# snowflake_r2.net
KiCad netlist of a schematic drawn in Altium Designer
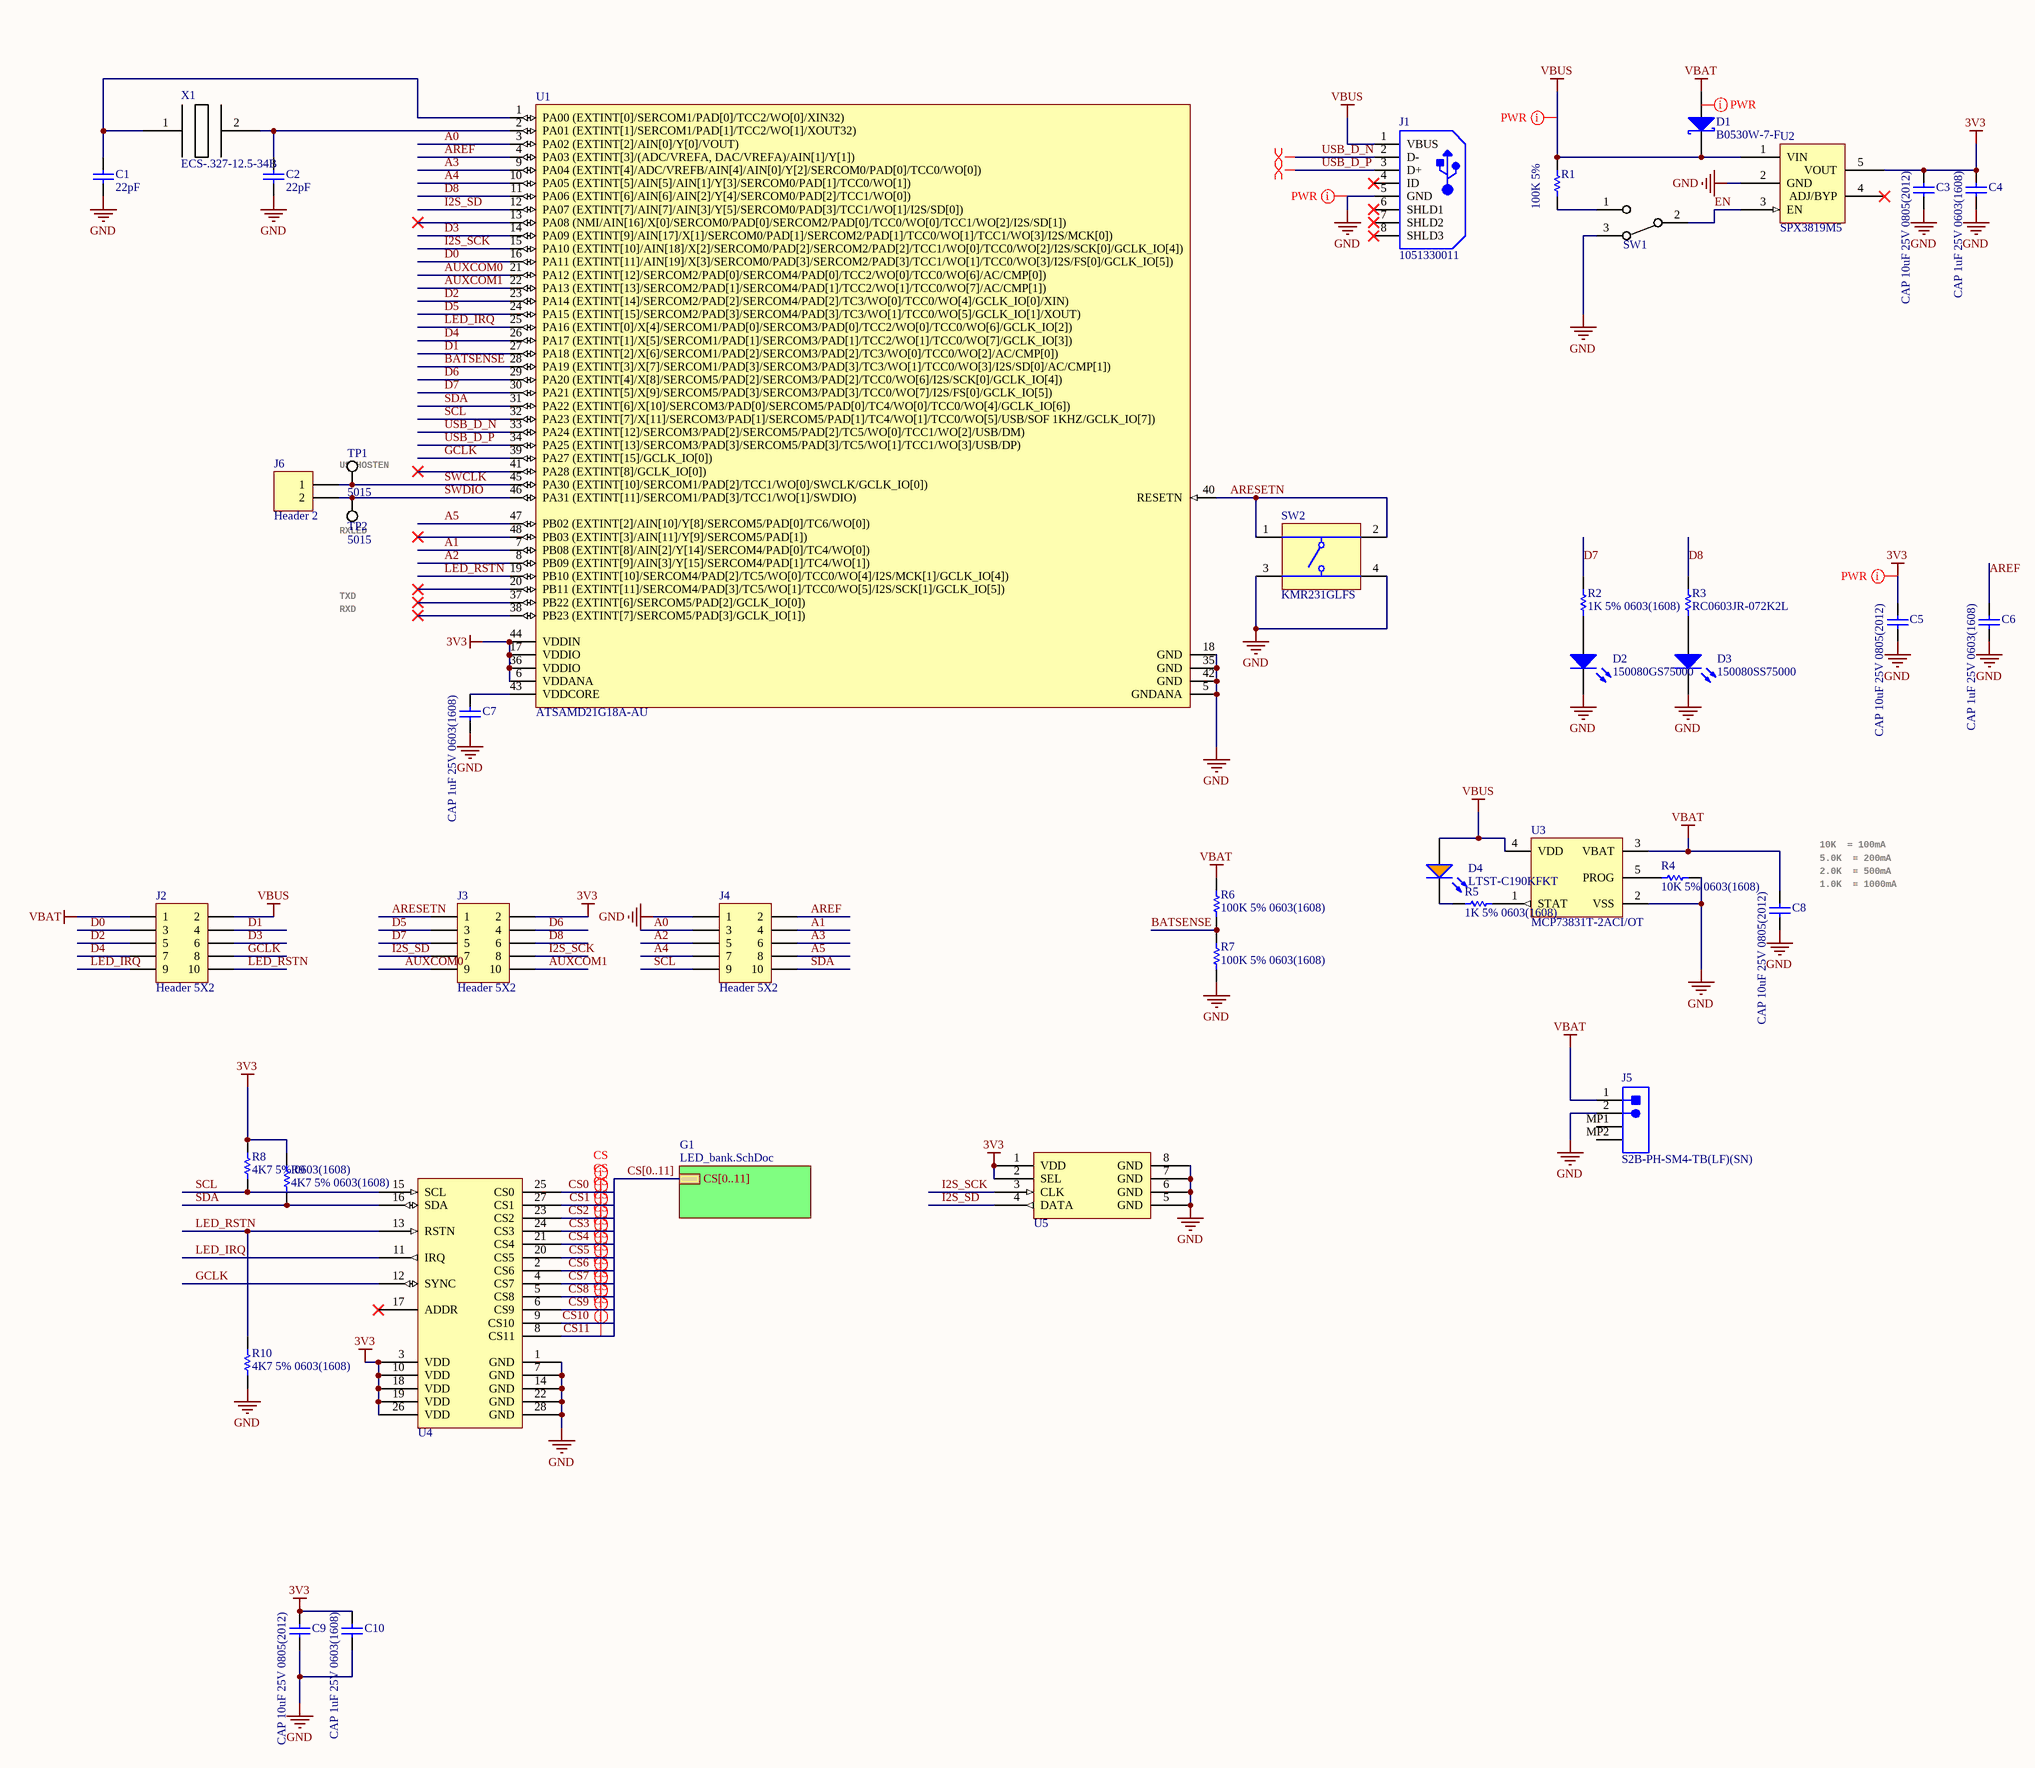
[diagram p0: snowflake_r2.SchDoc]

(export (version "E")
  (design (tool "Eeschema 10.0.6"))
  (components
    (comp (ref "C1")
      (value "22pF")
      (footprint "CAPC0603(1608)100_L")
      (description "0603 (1608 Metric) Chip Capacitor")
      (libsource (lib "Altium Content Vault") (part "CMP-1590-00005-1"))
    )
    (comp (ref "C2")
      (value "22pF")
      (footprint "CAPC0603(1608)100_L")
      (description "0603 (1608 Metric) Chip Capacitor")
      (libsource (lib "Altium Content Vault") (part "CAP_5"))
    )
    (comp (ref "C3")
      (value "CAP 10uF 25V 0805(2012)")
      (footprint "CAPC0805(2012)145_N")
      (description "CAP 10uF 25V ±10% 0805 (2012 Metric) Thickness 1.45mm SMD")
      (fields (field (name "TOLERANCE") "Â±10%"))
      (libsource (lib "Altium Content Vault") (part "CAP"))
    )
    (comp (ref "C4")
      (value "CAP 1uF 25V 0603(1608)")
      (footprint "CAPC0603(1608)100_M")
      (description "CAP 1uF 25V ±20% 0603 (1608 Metric) Thickness 1mm SMD")
      (fields (field (name "TOLERANCE") "Â±20%"))
      (libsource (lib "Altium Content Vault") (part "CAP"))
    )
    (comp (ref "C5")
      (value "CAP 10uF 25V 0805(2012)")
      (footprint "CAPC0805(2012)145_N")
      (description "CAP 10uF 25V ±10% 0805 (2012 Metric) Thickness 1.45mm SMD")
      (fields (field (name "TOLERANCE") "Â±10%"))
      (libsource (lib "Altium Content Vault") (part "CAP"))
    )
    (comp (ref "C6")
      (value "CAP 1uF 25V 0603(1608)")
      (footprint "CAPC0603(1608)100_M")
      (description "CAP 1uF 25V ±20% 0603 (1608 Metric) Thickness 1mm SMD")
      (fields (field (name "TOLERANCE") "Â±20%"))
      (libsource (lib "Altium Content Vault") (part "CAP"))
    )
    (comp (ref "C7")
      (value "CAP 1uF 25V 0603(1608)")
      (footprint "CAPC0603(1608)100_M")
      (description "CAP 1uF 25V ±20% 0603 (1608 Metric) Thickness 1mm SMD")
      (fields (field (name "TOLERANCE") "Â±20%"))
      (libsource (lib "Altium Content Vault") (part "CAP"))
    )
    (comp (ref "C8")
      (value "CAP 10uF 25V 0805(2012)")
      (footprint "CAPC0805(2012)145_N")
      (description "CAP 10uF 25V ±10% 0805 (2012 Metric) Thickness 1.45mm SMD")
      (fields (field (name "TOLERANCE") "Â±10%"))
      (libsource (lib "Altium Content Vault") (part "CAP"))
    )
    (comp (ref "C9")
      (value "CAP 10uF 25V 0805(2012)")
      (footprint "CAPC0805(2012)145_N")
      (description "CAP 10uF 25V ±10% 0805 (2012 Metric) Thickness 1.45mm SMD")
      (fields (field (name "TOLERANCE") "Â±10%"))
      (libsource (lib "Altium Content Vault") (part "CAP"))
    )
    (comp (ref "C10")
      (value "CAP 1uF 25V 0603(1608)")
      (footprint "CAPC0603(1608)100_M")
      (description "CAP 1uF 25V ±20% 0603 (1608 Metric) Thickness 1mm SMD")
      (fields (field (name "TOLERANCE") "Â±20%"))
      (libsource (lib "Altium Content Vault") (part "CAP"))
    )
    (comp (ref "D1")
      (value "B0530W-7-F")
      (footprint "DIOD-SOD-123-2-A_V")
      (description "Schottky Barrier Rectifier, 0.5 A, 30 V, -65 to 125 degC, 2-Pin SOD-123, RoHS, Tape and Reel")
      (fields (field (name "MANUFACTURER") "DiodesIncorporated"))
      (libsource (lib "Altium Content Vault") (part "DSKY-AK-2"))
    )
    (comp (ref "D2")
      (value "150080GS75000")
      (footprint "0805_A")
      (description "SMD mono-color Chip LED, WL-SMCW, Green")
      (fields (field (name "MANUFACTURER") "Wuerth Elektronik"))
      (libsource (lib "Altium Content Vault") (part "WE-LED_K1A2-2"))
    )
    (comp (ref "D3")
      (value "150080SS75000")
      (footprint "0805_A")
      (description "SMD mono-color Chip LED, WL-SMCW, Super Red")
      (fields (field (name "MANUFACTURER") "Wuerth Elektronik"))
      (libsource (lib "Altium Content Vault") (part "WE-LED_K1A2-2"))
    )
    (comp (ref "D4")
      (value "LTST-C190KFKT")
      (footprint "LTST-C190KFKT_V")
      (description "LED Uni-Color Orange, 75 mW, 30 mA, -35 to 85 degC, 2-Pin SMD, RoHS, Tape and Reel")
      (fields (field (name "TOLERANCE") "1%"))
      (libsource (lib "Altium Content Vault") (part "LED-ORANGE-AK-2"))
    )
    (comp (ref "J1")
      (value "1051330011")
      (footprint "MOLX-1051330011-5_V")
      (description "Micro-B USB Vertical Type, -30 to 85 degC, 5-Pin SMD, RoHS, Tape and Reel")
      (fields (field (name "MANUFACTURER") "Molex"))
      (libsource (lib "Altium Content Vault") (part "CMP-2000-05241-1"))
    )
    (comp (ref "J2")
      (value "Header 5X2")
      (footprint "HDR2X5")
      (description "Header, 5-Pin, Dual row")
      (fields (field (name "PUBLISHER") "Altium Limited"))
      (libsource (lib "Miscellaneous Connectors") (part "Header 5X2"))
    )
    (comp (ref "J3")
      (value "Header 5X2")
      (footprint "HDR2X5")
      (description "Header, 5-Pin, Dual row")
      (fields (field (name "PUBLISHER") "Altium Limited"))
      (libsource (lib "Miscellaneous Connectors") (part "Header 5X2"))
    )
    (comp (ref "J4")
      (value "Header 5X2")
      (footprint "HDR2X5")
      (description "Header, 5-Pin, Dual row")
      (fields (field (name "PUBLISHER") "Altium Limited"))
      (libsource (lib "Miscellaneous Connectors") (part "Header 5X2"))
    )
    (comp (ref "J5")
      (value "S2B-PH-SM4-TB(LF)(SN)")
      (footprint "JST- S2B-PH-SM4-TB(LF)(SN)-2_V")
      (description "Male Header, Pitch 2 mm, 1 x 2 Position, Height 5.5 mm, -25 to 85 degC, RoHS, Tape and Reel")
      (libsource (lib "Altium Content Vault") (part "CMP-1755-00001-1"))
    )
    (comp (ref "J6")
      (value "Header 2")
      (footprint "HDR1X2")
      (description "Header, 2-Pin")
      (fields (field (name "PUBLISHER") "Altium Limited"))
      (libsource (lib "Miscellaneous Connectors") (part "Header 2"))
    )
    (comp (ref "R1")
      (value "100K 5%")
      (footprint "RESC0603(1608)_N")
      (description "100K 0.1W 5% 0603 (1608 Metric)  SMD")
      (fields (field (name "TOLERANCE") "5 %") (field (name "POWER") "0.1 W"))
      (libsource (lib "Altium Content Vault") (part "RES"))
    )
    (comp (ref "R2")
      (value "1K 5% 0603(1608)")
      (footprint "RESC0603(1608)_L")
      (description "1K 0.1W 5% 0603 (1608 Metric)  SMD")
      (fields (field (name "TOLERANCE") "5 %") (field (name "POWER") "0.1 W"))
      (libsource (lib "Altium Content Vault") (part "RES"))
    )
    (comp (ref "R3")
      (value "RC0603JR-072K2L")
      (footprint "RESC1608X55X25LL10T15")
      (description "Chip Resistor, 2.2 KOhm, +/- 5%, 0.1 W, -55 to 155 degC, 0603 (1608 Metric), RoHS, Tape and Reel")
      (fields (field (name "MANUFACTURER") "Yageo") (field (name "TOLERANCE") "5%"))
      (libsource (lib "Altium Content Vault") (part "RES-2"))
    )
    (comp (ref "R4")
      (value "10K 5% 0603(1608)")
      (footprint "RESC0603(1608)_N")
      (description "10K 0.1W 5% 0603 (1608 Metric)  SMD")
      (fields (field (name "TOLERANCE") "5 %") (field (name "POWER") "0.1 W"))
      (libsource (lib "Altium Content Vault") (part "RES"))
    )
    (comp (ref "R5")
      (value "1K 5% 0603(1608)")
      (footprint "RESC0603(1608)_L")
      (description "1K 0.1W 5% 0603 (1608 Metric)  SMD")
      (fields (field (name "TOLERANCE") "5 %") (field (name "POWER") "0.1 W"))
      (libsource (lib "Altium Content Vault") (part "RES"))
    )
    (comp (ref "R6")
      (value "100K 5% 0603(1608)")
      (footprint "RESC0603(1608)_N")
      (description "100K 0.1W 5% 0603 (1608 Metric)  SMD")
      (fields (field (name "TOLERANCE") "5 %") (field (name "POWER") "0.1 W"))
      (libsource (lib "Altium Content Vault") (part "RES"))
    )
    (comp (ref "R7")
      (value "100K 5% 0603(1608)")
      (footprint "RESC0603(1608)_N")
      (description "100K 0.1W 5% 0603 (1608 Metric)  SMD")
      (fields (field (name "TOLERANCE") "5 %") (field (name "POWER") "0.1 W"))
      (libsource (lib "Altium Content Vault") (part "RES"))
    )
    (comp (ref "R8")
      (value "4K7 5% 0603(1608)")
      (footprint "RESC0603(1608)_N")
      (description "4K7 0.1W 5% 0603 (1608 Metric)  SMD")
      (fields (field (name "TOLERANCE") "5 %") (field (name "POWER") "0.1 W"))
      (libsource (lib "Altium Content Vault") (part "RES"))
    )
    (comp (ref "R9")
      (value "4K7 5% 0603(1608)")
      (footprint "RESC0603(1608)_N")
      (description "4K7 0.1W 5% 0603 (1608 Metric)  SMD")
      (fields (field (name "TOLERANCE") "5 %") (field (name "POWER") "0.1 W"))
      (libsource (lib "Altium Content Vault") (part "RES"))
    )
    (comp (ref "R10")
      (value "4K7 5% 0603(1608)")
      (footprint "RESC0603(1608)_N")
      (description "4K7 0.1W 5% 0603 (1608 Metric)  SMD")
      (fields (field (name "TOLERANCE") "5 %") (field (name "POWER") "0.1 W"))
      (libsource (lib "Altium Content Vault") (part "RES"))
    )
    (comp (ref "SW1")
      (value "JS102011JCQN")
      (footprint "JS102011JCQN")
      (description "SWITCH SPDT PCB")
      (libsource (lib "snowflake") (part "SW-SPDT"))
    )
    (comp (ref "SW2")
      (value "KMR231GLFS")
      (footprint "CKCP-KMR231GLFS")
      (description "Switch Tactile, SPST, 50 mA, 32 V, -40 to 85 degC, 4-Pin SMD, RoHS, Tape and Reel")
      (fields (field (name "MANUFACTURER") "C&K Components"))
      (libsource (lib "Altium Content Vault") (part "SW-SPST-4_A"))
    )
    (comp (ref "TP1")
      (value "5015")
      (footprint "KSTN-5015_V")
      (description "Test Point, White, SMT")
      (fields (field (name "MANUFACTURER") "Keystone"))
      (libsource (lib "Altium Content Vault") (part "TESTPOINT_WHITE"))
    )
    (comp (ref "TP2")
      (value "5015")
      (footprint "KSTN-5015_V")
      (description "Test Point, White, SMT")
      (fields (field (name "MANUFACTURER") "Keystone"))
      (libsource (lib "Altium Content Vault") (part "TESTPOINT_WHITE"))
    )
    (comp (ref "U1")
      (value "ATSAMD21G18A-AU")
      (footprint "ATML-TQFP48_M")
      (fields (field (name "MANUFACTURER") "Atmel"))
      (libsource (lib "Altium Content Vault") (part "ATML-ATSAMD21G18_17_16_15A-TQFP48"))
    )
    (comp (ref "U2")
      (value "SPX3819M5")
      (footprint "SOT95P280X145-5N")
      (description "IC REG LINEAR 3.3V 500MA SOT23-5")
      (libsource (lib "snowflake") (part "SPX3819M5"))
    )
    (comp (ref "U3")
      (value "MCP73831T-2ACI/OT")
      (footprint "SOT-23-OT5_M")
      (libsource (lib "Altium Content Vault") (part "PM-BM-MCP73831-SOT5"))
    )
    (comp (ref "U4")
      (value "AS1130_BTST")
      (footprint "TSOP65P640X120-28N")
      (description "IC LED DRVR MATRIX 28TSSOP")
      (libsource (lib "snowflake") (part "AS1130_BTST"))
    )
    (comp (ref "U5")
      (value "SPK0415HM4H-B-7")
      (footprint "SPK0415HM4H-B-7")
      (description "MIC MEMS DIGITAL PDM OMNI -26DB")
      (libsource (lib "snowflake") (part "SPK0415HM4H-B-7"))
    )
    (comp (ref "X1")
      (value "ECS-.327-12.5-34B")
      (footprint "ECX-31B")
      (description "XTAL 32.768KHZ 12.5PF SMD")
      (libsource (lib "snowflake") (part "ECS-.327-12.5-34B"))
    )
  )
  (nets
    (net (code "1") (name "/A0") (class "Default")
      (node (ref "J4") (pin "3") (pinfunction "3_3") (pintype "passive"))
      (node (ref "U1") (pin "3") (pinfunction "PA02_(EXTINT[2]/AIN[0]/Y[0]/VOUT)_3") (pintype "bidirectional"))
    )
    (net (code "2") (name "/A1") (class "Default")
      (node (ref "J4") (pin "4") (pinfunction "4_4") (pintype "passive"))
      (node (ref "U1") (pin "7") (pinfunction "PB08_(EXTINT[8]/AIN[2]/Y[14]/SERCOM4/PAD[0]/TC4/WO[0])_7") (pintype "bidirectional"))
    )
    (net (code "3") (name "/A2") (class "Default")
      (node (ref "J4") (pin "5") (pinfunction "5_5") (pintype "passive"))
      (node (ref "U1") (pin "8") (pinfunction "PB09_(EXTINT[9]/AIN[3]/Y[15]/SERCOM4/PAD[1]/TC4/WO[1])_8") (pintype "bidirectional"))
    )
    (net (code "4") (name "/A3") (class "Default")
      (node (ref "J4") (pin "6") (pinfunction "6_6") (pintype "passive"))
      (node (ref "U1") (pin "9") (pinfunction "PA04_(EXTINT[4]/ADC/VREFB/AIN[4]/AIN[0]/Y[2]/SERCOM0/PAD[0]/TCC0/WO[0])_9") (pintype "bidirectional"))
    )
    (net (code "5") (name "/A4") (class "Default")
      (node (ref "J4") (pin "7") (pinfunction "7_7") (pintype "passive"))
      (node (ref "U1") (pin "10") (pinfunction "PA05_(EXTINT[5]/AIN[5]/AIN[1]/Y[3]/SERCOM0/PAD[1]/TCC0/WO[1])_10") (pintype "bidirectional"))
    )
    (net (code "6") (name "/A5") (class "Default")
      (node (ref "J4") (pin "8") (pinfunction "8_8") (pintype "passive"))
      (node (ref "U1") (pin "47") (pinfunction "PB02_(EXTINT[2]/AIN[10]/Y[8]/SERCOM5/PAD[0]/TC6/WO[0])_47") (pintype "bidirectional"))
    )
    (net (code "7") (name "/AREF") (class "Default")
      (node (ref "C6") (pin "2") (pinfunction "2_2") (pintype "passive"))
      (node (ref "J4") (pin "2") (pinfunction "2_2") (pintype "passive"))
      (node (ref "U1") (pin "4") (pinfunction "PA03_(EXTINT[3]/(ADC/VREFA,_DAC/VREFA)/AIN[1]/Y[1])_4") (pintype "bidirectional"))
    )
    (net (code "8") (name "/ARESETN") (class "Default")
      (node (ref "J3") (pin "1") (pinfunction "1_1") (pintype "passive"))
      (node (ref "SW2") (pin "1") (pinfunction "1_1") (pintype "passive"))
      (node (ref "SW2") (pin "2") (pinfunction "2_2") (pintype "passive"))
      (node (ref "U1") (pin "40") (pinfunction "RESETN_40") (pintype "input"))
    )
    (net (code "9") (name "/AUXCOM0") (class "Default")
      (node (ref "J3") (pin "9") (pinfunction "9_9") (pintype "passive"))
      (node (ref "U1") (pin "21") (pinfunction "PA12_(EXTINT[12]/SERCOM2/PAD[0]/SERCOM4/PAD[0]/TCC2/WO[0]/TCC0/WO[6]/AC/CMP[0])_21") (pintype "bidirectional"))
    )
    (net (code "10") (name "/AUXCOM1") (class "Default")
      (node (ref "J3") (pin "10") (pinfunction "10_10") (pintype "passive"))
      (node (ref "U1") (pin "22") (pinfunction "PA13_(EXTINT[13]/SERCOM2/PAD[1]/SERCOM4/PAD[1]/TCC2/WO[1]/TCC0/WO[7]/AC/CMP[1])_22") (pintype "bidirectional"))
    )
    (net (code "11") (name "/BATSENSE") (class "Default")
      (node (ref "R6") (pin "1") (pinfunction "1_1") (pintype "passive"))
      (node (ref "R7") (pin "2") (pinfunction "2_2") (pintype "passive"))
      (node (ref "U1") (pin "28") (pinfunction "PA19_(EXTINT[3]/X[7]/SERCOM1/PAD[3]/SERCOM3/PAD[3]/TC3/WO[1]/TCC0/WO[3]/I2S/SD[0]/AC/CMP[1])_28") (pintype "bidirectional"))
    )
    (net (code "12") (name "/CS0") (class "Default")
      (node (ref "U4") (pin "25") (pinfunction "CS0_25") (pintype "passive"))
    )
    (net (code "13") (name "/CS1") (class "Default")
      (node (ref "U4") (pin "27") (pinfunction "CS1_27") (pintype "passive"))
    )
    (net (code "14") (name "/CS2") (class "Default")
      (node (ref "U4") (pin "23") (pinfunction "CS2_23") (pintype "passive"))
    )
    (net (code "15") (name "/CS3") (class "Default")
      (node (ref "U4") (pin "24") (pinfunction "CS3_24") (pintype "passive"))
    )
    (net (code "16") (name "/CS4") (class "Default")
      (node (ref "U4") (pin "21") (pinfunction "CS4_21") (pintype "passive"))
    )
    (net (code "17") (name "/CS5") (class "Default")
      (node (ref "U4") (pin "20") (pinfunction "CS5_20") (pintype "passive"))
    )
    (net (code "18") (name "/CS6") (class "Default")
      (node (ref "U4") (pin "2") (pinfunction "CS6_2") (pintype "passive"))
    )
    (net (code "19") (name "/CS7") (class "Default")
      (node (ref "U4") (pin "4") (pinfunction "CS7_4") (pintype "passive"))
    )
    (net (code "20") (name "/CS8") (class "Default")
      (node (ref "U4") (pin "5") (pinfunction "CS8_5") (pintype "passive"))
    )
    (net (code "21") (name "/CS9") (class "Default")
      (node (ref "U4") (pin "6") (pinfunction "CS9_6") (pintype "passive"))
    )
    (net (code "22") (name "/CS10") (class "Default")
      (node (ref "U4") (pin "9") (pinfunction "CS10_9") (pintype "passive"))
    )
    (net (code "23") (name "/CS11") (class "Default")
      (node (ref "U4") (pin "8") (pinfunction "CS11_8") (pintype "passive"))
    )
    (net (code "25") (name "/D0") (class "Default")
      (node (ref "J2") (pin "3") (pinfunction "3_3") (pintype "passive"))
      (node (ref "U1") (pin "16") (pinfunction "PA11_(EXTINT[11]/AIN[19]/X[3]/SERCOM0/PAD[3]/SERCOM2/PAD[3]/TCC1/WO[1]/TCC0/WO[3]/I2S/FS[0]/GCLK_IO[5])_16") (pintype "bidirectional"))
    )
    (net (code "26") (name "/D1") (class "Default")
      (node (ref "J2") (pin "4") (pinfunction "4_4") (pintype "passive"))
      (node (ref "U1") (pin "27") (pinfunction "PA18_(EXTINT[2]/X[6]/SERCOM1/PAD[2]/SERCOM3/PAD[2]/TC3/WO[0]/TCC0/WO[2]/AC/CMP[0])_27") (pintype "bidirectional"))
    )
    (net (code "27") (name "/D2") (class "Default")
      (node (ref "J2") (pin "5") (pinfunction "5_5") (pintype "passive"))
      (node (ref "U1") (pin "23") (pinfunction "PA14_(EXTINT[14]/SERCOM2/PAD[2]/SERCOM4/PAD[2]/TC3/WO[0]/TCC0/WO[4]/GCLK_IO[0]/XIN)_23") (pintype "bidirectional"))
    )
    (net (code "28") (name "/D3") (class "Default")
      (node (ref "J2") (pin "6") (pinfunction "6_6") (pintype "passive"))
      (node (ref "U1") (pin "14") (pinfunction "PA09_(EXTINT[9]/AIN[17]/X[1]/SERCOM0/PAD[1]/SERCOM2/PAD[1]/TCC0/WO[1]/TCC1/WO[3]/I2S/MCK[0])_14") (pintype "bidirectional"))
    )
    (net (code "29") (name "/D4") (class "Default")
      (node (ref "J2") (pin "7") (pinfunction "7_7") (pintype "passive"))
      (node (ref "U1") (pin "26") (pinfunction "PA17_(EXTINT[1]/X[5]/SERCOM1/PAD[1]/SERCOM3/PAD[1]/TCC2/WO[1]/TCC0/WO[7]/GCLK_IO[3])_26") (pintype "bidirectional"))
    )
    (net (code "30") (name "/D5") (class "Default")
      (node (ref "J3") (pin "3") (pinfunction "3_3") (pintype "passive"))
      (node (ref "U1") (pin "24") (pinfunction "PA15_(EXTINT[15]/SERCOM2/PAD[3]/SERCOM4/PAD[3]/TC3/WO[1]/TCC0/WO[5]/GCLK_IO[1]/XOUT)_24") (pintype "bidirectional"))
    )
    (net (code "31") (name "/D6") (class "Default")
      (node (ref "J3") (pin "4") (pinfunction "4_4") (pintype "passive"))
      (node (ref "U1") (pin "29") (pinfunction "PA20_(EXTINT[4]/X[8]/SERCOM5/PAD[2]/SERCOM3/PAD[2]/TCC0/WO[6]/I2S/SCK[0]/GCLK_IO[4])_29") (pintype "bidirectional"))
    )
    (net (code "32") (name "/D7") (class "Default")
      (node (ref "J3") (pin "5") (pinfunction "5_5") (pintype "passive"))
      (node (ref "R2") (pin "2") (pinfunction "2_2") (pintype "passive"))
      (node (ref "U1") (pin "30") (pinfunction "PA21_(EXTINT[5]/X[9]/SERCOM5/PAD[3]/SERCOM3/PAD[3]/TCC0/WO[7]/I2S/FS[0]/GCLK_IO[5])_30") (pintype "bidirectional"))
    )
    (net (code "33") (name "/D8") (class "Default")
      (node (ref "J3") (pin "6") (pinfunction "6_6") (pintype "passive"))
      (node (ref "R3") (pin "2") (pinfunction "2_2") (pintype "passive"))
      (node (ref "U1") (pin "11") (pinfunction "PA06_(EXTINT[6]/AIN[6]/AIN[2]/Y[4]/SERCOM0/PAD[2]/TCC1/WO[0])_11") (pintype "bidirectional"))
    )
    (net (code "34") (name "/EN") (class "Default")
      (node (ref "SW1") (pin "2") (pinfunction "2_2") (pintype "passive"))
      (node (ref "U2") (pin "3") (pinfunction "EN_3") (pintype "input"))
    )
    (net (code "35") (name "/GCLK") (class "Default")
      (node (ref "J2") (pin "8") (pinfunction "8_8") (pintype "passive"))
      (node (ref "U1") (pin "39") (pinfunction "PA27_(EXTINT[15]/GCLK_IO[0])_39") (pintype "bidirectional"))
      (node (ref "U4") (pin "12") (pinfunction "SYNC_12") (pintype "bidirectional"))
    )
    (net (code "36") (name "/I2S_SCK") (class "Default")
      (node (ref "J3") (pin "8") (pinfunction "8_8") (pintype "passive"))
      (node (ref "U1") (pin "15") (pinfunction "PA10_(EXTINT[10]/AIN[18]/X[2]/SERCOM0/PAD[2]/SERCOM2/PAD[2]/TCC1/WO[0]/TCC0/WO[2]/I2S/SCK[0]/GCLK_IO[4])_15") (pintype "bidirectional"))
      (node (ref "U5") (pin "3") (pinfunction "CLK_3") (pintype "input"))
    )
    (net (code "37") (name "/I2S_SD") (class "Default")
      (node (ref "J3") (pin "7") (pinfunction "7_7") (pintype "passive"))
      (node (ref "U1") (pin "12") (pinfunction "PA07_(EXTINT[7]/AIN[7]/AIN[3]/Y[5]/SERCOM0/PAD[3]/TCC1/WO[1]/I2S/SD[0])_12") (pintype "bidirectional"))
      (node (ref "U5") (pin "4") (pinfunction "DATA_4") (pintype "output"))
    )
    (net (code "38") (name "/LED_IRQ") (class "Default")
      (node (ref "J2") (pin "9") (pinfunction "9_9") (pintype "passive"))
      (node (ref "U1") (pin "25") (pinfunction "PA16_(EXTINT[0]/X[4]/SERCOM1/PAD[0]/SERCOM3/PAD[0]/TCC2/WO[0]/TCC0/WO[6]/GCLK_IO[2])_25") (pintype "bidirectional"))
      (node (ref "U4") (pin "11") (pinfunction "IRQ_11") (pintype "output"))
    )
    (net (code "39") (name "/LED_RSTN") (class "Default")
      (node (ref "J2") (pin "10") (pinfunction "10_10") (pintype "passive"))
      (node (ref "R10") (pin "2") (pinfunction "2_2") (pintype "passive"))
      (node (ref "U1") (pin "19") (pinfunction "PB10_(EXTINT[10]/SERCOM4/PAD[2]/TC5/WO[0]/TCC0/WO[4]/I2S/MCK[1]/GCLK_IO[4])_19") (pintype "bidirectional"))
      (node (ref "U4") (pin "13") (pinfunction "RSTN_13") (pintype "input"))
    )
    (net (code "40") (name "/SCL") (class "Default")
      (node (ref "J4") (pin "9") (pinfunction "9_9") (pintype "passive"))
      (node (ref "R8") (pin "1") (pinfunction "1_1") (pintype "passive"))
      (node (ref "U1") (pin "32") (pinfunction "PA23_(EXTINT[7]/X[11]/SERCOM3/PAD[1]/SERCOM5/PAD[1]/TC4/WO[1]/TCC0/WO[5]/USB/SOF_1KHZ/GCLK_IO[7])_32") (pintype "bidirectional"))
      (node (ref "U4") (pin "15") (pinfunction "SCL_15") (pintype "input"))
    )
    (net (code "41") (name "/SDA") (class "Default")
      (node (ref "J4") (pin "10") (pinfunction "10_10") (pintype "passive"))
      (node (ref "R9") (pin "1") (pinfunction "1_1") (pintype "passive"))
      (node (ref "U1") (pin "31") (pinfunction "PA22_(EXTINT[6]/X[10]/SERCOM3/PAD[0]/SERCOM5/PAD[0]/TC4/WO[0]/TCC0/WO[4]/GCLK_IO[6])_31") (pintype "bidirectional"))
      (node (ref "U4") (pin "16") (pinfunction "SDA_16") (pintype "bidirectional"))
    )
    (net (code "42") (name "/SWCLK") (class "Default")
      (node (ref "J6") (pin "1") (pinfunction "1_1") (pintype "passive"))
      (node (ref "TP1") (pin "1") (pinfunction "1_1") (pintype "passive"))
      (node (ref "U1") (pin "45") (pinfunction "PA30_(EXTINT[10]/SERCOM1/PAD[2]/TCC1/WO[0]/SWCLK/GCLK_IO[0])_45") (pintype "bidirectional"))
    )
    (net (code "43") (name "/SWDIO") (class "Default")
      (node (ref "J6") (pin "2") (pinfunction "2_2") (pintype "passive"))
      (node (ref "TP2") (pin "1") (pinfunction "1_1") (pintype "passive"))
      (node (ref "U1") (pin "46") (pinfunction "PA31_(EXTINT[11]/SERCOM1/PAD[3]/TCC1/WO[1]/SWDIO)_46") (pintype "bidirectional"))
    )
    (net (code "44") (name "/USB_D_N") (class "Default")
      (node (ref "J1") (pin "2") (pinfunction "D-_2") (pintype "passive"))
      (node (ref "U1") (pin "33") (pinfunction "PA24_(EXTINT[12]/SERCOM3/PAD[2]/SERCOM5/PAD[2]/TC5/WO[0]/TCC1/WO[2]/USB/DM)_33") (pintype "bidirectional"))
    )
    (net (code "45") (name "/USB_D_P") (class "Default")
      (node (ref "J1") (pin "3") (pinfunction "D+_3") (pintype "passive"))
      (node (ref "U1") (pin "34") (pinfunction "PA25_(EXTINT[13]/SERCOM3/PAD[3]/SERCOM5/PAD[3]/TC5/WO[1]/TCC1/WO[3]/USB/DP)_34") (pintype "bidirectional"))
    )
    (net (code "46") (name "3V3") (class "Default")
      (node (ref "C10") (pin "2") (pinfunction "2_2") (pintype "passive"))
      (node (ref "C3") (pin "2") (pinfunction "2_2") (pintype "passive"))
      (node (ref "C4") (pin "2") (pinfunction "2_2") (pintype "passive"))
      (node (ref "C5") (pin "2") (pinfunction "2_2") (pintype "passive"))
      (node (ref "C9") (pin "2") (pinfunction "2_2") (pintype "passive"))
      (node (ref "J3") (pin "2") (pinfunction "2_2") (pintype "passive"))
      (node (ref "R8") (pin "2") (pinfunction "2_2") (pintype "passive"))
      (node (ref "R9") (pin "2") (pinfunction "2_2") (pintype "passive"))
      (node (ref "U1") (pin "17") (pinfunction "VDDIO_17") (pintype "power_in"))
      (node (ref "U1") (pin "36") (pinfunction "VDDIO_36") (pintype "power_in"))
      (node (ref "U1") (pin "44") (pinfunction "VDDIN_44") (pintype "power_in"))
      (node (ref "U1") (pin "6") (pinfunction "VDDANA_6") (pintype "power_in"))
      (node (ref "U2") (pin "5") (pinfunction "VOUT_5") (pintype "power_in"))
      (node (ref "U4") (pin "10") (pinfunction "VDD_10") (pintype "power_in"))
      (node (ref "U4") (pin "18") (pinfunction "VDD_18") (pintype "power_in"))
      (node (ref "U4") (pin "19") (pinfunction "VDD_19") (pintype "power_in"))
      (node (ref "U4") (pin "26") (pinfunction "VDD_26") (pintype "power_in"))
      (node (ref "U4") (pin "3") (pinfunction "VDD_3") (pintype "power_in"))
      (node (ref "U5") (pin "1") (pinfunction "VDD_1") (pintype "power_in"))
      (node (ref "U5") (pin "2") (pinfunction "SEL_2") (pintype "passive"))
    )
    (net (code "47") (name "GND") (class "Default")
      (node (ref "C1") (pin "1") (pinfunction "1_1") (pintype "passive"))
      (node (ref "C10") (pin "1") (pinfunction "1_1") (pintype "passive"))
      (node (ref "C2") (pin "1") (pinfunction "1_1") (pintype "passive"))
      (node (ref "C3") (pin "1") (pinfunction "1_1") (pintype "passive"))
      (node (ref "C4") (pin "1") (pinfunction "1_1") (pintype "passive"))
      (node (ref "C5") (pin "1") (pinfunction "1_1") (pintype "passive"))
      (node (ref "C6") (pin "1") (pinfunction "1_1") (pintype "passive"))
      (node (ref "C7") (pin "1") (pinfunction "1_1") (pintype "passive"))
      (node (ref "C8") (pin "1") (pinfunction "1_1") (pintype "passive"))
      (node (ref "C9") (pin "1") (pinfunction "1_1") (pintype "passive"))
      (node (ref "D2") (pin "1") (pinfunction "K_1") (pintype "passive"))
      (node (ref "D3") (pin "1") (pinfunction "K_1") (pintype "passive"))
      (node (ref "J1") (pin "5") (pinfunction "GND_5") (pintype "passive"))
      (node (ref "J4") (pin "1") (pinfunction "1_1") (pintype "passive"))
      (node (ref "J5") (pin "2") (pinfunction "2_2") (pintype "passive"))
      (node (ref "R10") (pin "1") (pinfunction "1_1") (pintype "passive"))
      (node (ref "R4") (pin "1") (pinfunction "1_1") (pintype "passive"))
      (node (ref "R7") (pin "1") (pinfunction "1_1") (pintype "passive"))
      (node (ref "SW1") (pin "3") (pinfunction "A1_3") (pintype "passive"))
      (node (ref "SW2") (pin "3") (pinfunction "3_3") (pintype "passive"))
      (node (ref "SW2") (pin "4") (pinfunction "4_4") (pintype "passive"))
      (node (ref "U1") (pin "18") (pinfunction "GND_18") (pintype "power_in"))
      (node (ref "U1") (pin "35") (pinfunction "GND_35") (pintype "power_in"))
      (node (ref "U1") (pin "42") (pinfunction "GND_42") (pintype "power_in"))
      (node (ref "U1") (pin "5") (pinfunction "GNDANA_5") (pintype "power_in"))
      (node (ref "U2") (pin "2") (pinfunction "GND_2") (pintype "power_in"))
      (node (ref "U3") (pin "2") (pinfunction "VSS_2") (pintype "power_in"))
      (node (ref "U4") (pin "1") (pinfunction "GND_1") (pintype "power_in"))
      (node (ref "U4") (pin "14") (pinfunction "GND_14") (pintype "power_in"))
      (node (ref "U4") (pin "22") (pinfunction "GND_22") (pintype "power_in"))
      (node (ref "U4") (pin "28") (pinfunction "GND_28") (pintype "power_in"))
      (node (ref "U4") (pin "7") (pinfunction "GND_7") (pintype "power_in"))
      (node (ref "U5") (pin "5") (pinfunction "GND_5") (pintype "power_in"))
      (node (ref "U5") (pin "6") (pinfunction "GND_6") (pintype "power_in"))
      (node (ref "U5") (pin "7") (pinfunction "GND_7") (pintype "power_in"))
      (node (ref "U5") (pin "8") (pinfunction "GND_8") (pintype "power_in"))
    )
    (net (code "48") (name "Net-(D2-A)") (class "Default")
      (node (ref "D2") (pin "2") (pinfunction "A_2") (pintype "passive"))
      (node (ref "R2") (pin "1") (pinfunction "1_1") (pintype "passive"))
    )
    (net (code "49") (name "Net-(D3-A)") (class "Default")
      (node (ref "D3") (pin "2") (pinfunction "A_2") (pintype "passive"))
      (node (ref "R3") (pin "1") (pinfunction "1_1") (pintype "passive"))
    )
    (net (code "50") (name "Net-(D4-K)") (class "Default")
      (node (ref "D4") (pin "2") (pinfunction "K_2") (pintype "passive"))
      (node (ref "R5") (pin "2") (pinfunction "2_2") (pintype "passive"))
    )
    (net (code "51") (name "Net-(SW1-B1)") (class "Default")
      (node (ref "R1") (pin "1") (pinfunction "1_1") (pintype "passive"))
      (node (ref "SW1") (pin "1") (pinfunction "B1_1") (pintype "passive"))
    )
    (net (code "52") (name "Net-(U1-PA00_(EXTINT[0]{slash}SERCOM1{slash}PAD[0]{slash}TCC2{slash}WO[0]{slash}XIN32))") (class "Default")
      (node (ref "C1") (pin "2") (pinfunction "2_2") (pintype "passive"))
      (node (ref "U1") (pin "1") (pinfunction "PA00_(EXTINT[0]/SERCOM1/PAD[0]/TCC2/WO[0]/XIN32)_1") (pintype "bidirectional"))
      (node (ref "X1") (pin "1") (pinfunction "1_1") (pintype "passive"))
    )
    (net (code "53") (name "Net-(U1-PA01_(EXTINT[1]{slash}SERCOM1{slash}PAD[1]{slash}TCC2{slash}WO[1]{slash}XOUT32))") (class "Default")
      (node (ref "C2") (pin "2") (pinfunction "2_2") (pintype "passive"))
      (node (ref "U1") (pin "2") (pinfunction "PA01_(EXTINT[1]/SERCOM1/PAD[1]/TCC2/WO[1]/XOUT32)_2") (pintype "bidirectional"))
      (node (ref "X1") (pin "2") (pinfunction "2_2") (pintype "passive"))
    )
    (net (code "54") (name "Net-(U1-VDDCORE)") (class "Default")
      (node (ref "C7") (pin "2") (pinfunction "2_2") (pintype "passive"))
      (node (ref "U1") (pin "43") (pinfunction "VDDCORE_43") (pintype "power_in"))
    )
    (net (code "55") (name "Net-(U3-PROG)") (class "Default")
      (node (ref "R4") (pin "2") (pinfunction "2_2") (pintype "passive"))
      (node (ref "U3") (pin "5") (pinfunction "PROG_5") (pintype "passive"))
    )
    (net (code "56") (name "Net-(U3-STAT)") (class "Default")
      (node (ref "R5") (pin "1") (pinfunction "1_1") (pintype "passive"))
      (node (ref "U3") (pin "1") (pinfunction "STAT_1") (pintype "output"))
    )
    (net (code "57") (name "VBAT") (class "Default")
      (node (ref "C8") (pin "2") (pinfunction "2_2") (pintype "passive"))
      (node (ref "D1") (pin "1") (pinfunction "A_1") (pintype "passive"))
      (node (ref "J2") (pin "1") (pinfunction "1_1") (pintype "passive"))
      (node (ref "J5") (pin "1") (pinfunction "1_1") (pintype "passive"))
      (node (ref "R6") (pin "2") (pinfunction "2_2") (pintype "passive"))
      (node (ref "U3") (pin "3") (pinfunction "VBAT_3") (pintype "power_in"))
    )
    (net (code "58") (name "VBUS") (class "Default")
      (node (ref "D1") (pin "2") (pinfunction "K_2") (pintype "passive"))
      (node (ref "D4") (pin "1") (pinfunction "A_1") (pintype "passive"))
      (node (ref "J1") (pin "1") (pinfunction "VBUS_1") (pintype "passive"))
      (node (ref "J2") (pin "2") (pinfunction "2_2") (pintype "passive"))
      (node (ref "R1") (pin "2") (pinfunction "2_2") (pintype "passive"))
      (node (ref "U2") (pin "1") (pinfunction "VIN_1") (pintype "power_in"))
      (node (ref "U3") (pin "4") (pinfunction "VDD_4") (pintype "power_in"))
    )
    (net (code "59") (name "unconnected-(J1-ID-Pad4)") (class "Default")
      (node (ref "J1") (pin "4") (pinfunction "ID_4") (pintype "passive+no_connect"))
    )
    (net (code "60") (name "unconnected-(J1-SHLD1-Pad6)") (class "Default")
      (node (ref "J1") (pin "6") (pinfunction "SHLD1_6") (pintype "passive+no_connect"))
    )
    (net (code "61") (name "unconnected-(J1-SHLD2-Pad7)") (class "Default")
      (node (ref "J1") (pin "7") (pinfunction "SHLD2_7") (pintype "passive+no_connect"))
    )
    (net (code "62") (name "unconnected-(J1-SHLD3-Pad8)") (class "Default")
      (node (ref "J1") (pin "8") (pinfunction "SHLD3_8") (pintype "passive+no_connect"))
    )
    (net (code "63") (name "unconnected-(J5-PadMP1)") (class "Default")
      (node (ref "J5") (pin "MP1") (pinfunction "MP1_MP1") (pintype "passive"))
    )
    (net (code "64") (name "unconnected-(J5-PadMP2)") (class "Default")
      (node (ref "J5") (pin "MP2") (pinfunction "MP2_MP2") (pintype "passive"))
    )
    (net (code "65") (name "unconnected-(U1-PA08_(NMI{slash}AIN[16]{slash}X[0]{slash}SERCOM0{slash}PAD[0]{slash}SERCOM2{slash}PAD[0]{slash}TCC0{slash}WO[0]{slash}TCC1{slash}WO[2]{slash}I2S{slash}SD[1])-Pad13)") (class "Default")
      (node (ref "U1") (pin "13") (pinfunction "PA08_(NMI/AIN[16]/X[0]/SERCOM0/PAD[0]/SERCOM2/PAD[0]/TCC0/WO[0]/TCC1/WO[2]/I2S/SD[1])_13") (pintype "bidirectional+no_connect"))
    )
    (net (code "66") (name "unconnected-(U1-PA28_(EXTINT[8]{slash}GCLK_IO[0])-Pad41)") (class "Default")
      (node (ref "U1") (pin "41") (pinfunction "PA28_(EXTINT[8]/GCLK_IO[0])_41") (pintype "bidirectional+no_connect"))
    )
    (net (code "67") (name "unconnected-(U1-PB03_(EXTINT[3]{slash}AIN[11]{slash}Y[9]{slash}SERCOM5{slash}PAD[1])-Pad48)") (class "Default")
      (node (ref "U1") (pin "48") (pinfunction "PB03_(EXTINT[3]/AIN[11]/Y[9]/SERCOM5/PAD[1])_48") (pintype "bidirectional+no_connect"))
    )
    (net (code "68") (name "unconnected-(U1-PB11_(EXTINT[11]{slash}SERCOM4{slash}PAD[3]{slash}TC5{slash}WO[1]{slash}TCC0{slash}WO[5]{slash}I2S{slash}SCK[1]{slash}GCLK_IO[5])-Pad20)") (class "Default")
      (node (ref "U1") (pin "20") (pinfunction "PB11_(EXTINT[11]/SERCOM4/PAD[3]/TC5/WO[1]/TCC0/WO[5]/I2S/SCK[1]/GCLK_IO[5])_20") (pintype "bidirectional+no_connect"))
    )
    (net (code "69") (name "unconnected-(U1-PB22_(EXTINT[6]{slash}SERCOM5{slash}PAD[2]{slash}GCLK_IO[0])-Pad37)") (class "Default")
      (node (ref "U1") (pin "37") (pinfunction "PB22_(EXTINT[6]/SERCOM5/PAD[2]/GCLK_IO[0])_37") (pintype "bidirectional+no_connect"))
    )
    (net (code "70") (name "unconnected-(U1-PB23_(EXTINT[7]{slash}SERCOM5{slash}PAD[3]{slash}GCLK_IO[1])-Pad38)") (class "Default")
      (node (ref "U1") (pin "38") (pinfunction "PB23_(EXTINT[7]/SERCOM5/PAD[3]/GCLK_IO[1])_38") (pintype "bidirectional+no_connect"))
    )
    (net (code "71") (name "unconnected-(U2-ADJ{slash}BYP-Pad4)") (class "Default")
      (node (ref "U2") (pin "4") (pinfunction "ADJ/BYP_4") (pintype "passive+no_connect"))
    )
    (net (code "72") (name "unconnected-(U4-ADDR-Pad17)") (class "Default")
      (node (ref "U4") (pin "17") (pinfunction "ADDR_17") (pintype "passive+no_connect"))
    )
  )
)
